# PCB_3.net
KiCad netlist of a schematic drawn in EAGLE
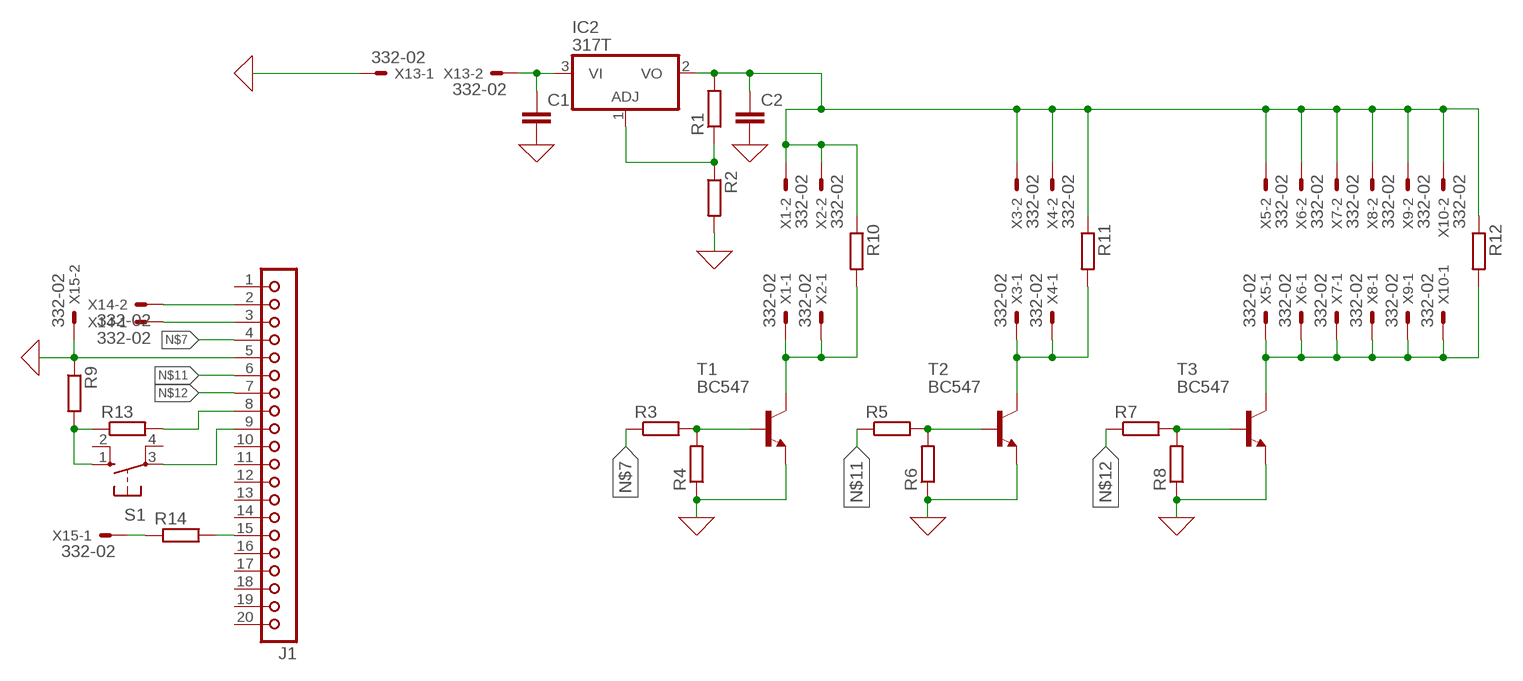
[diagram p0: schematic, sheet 1]

(export (version "E")
  (design (tool "Eeschema 10.0.6"))
  (components
    (comp (ref "C1")
      (value "C-EU050-025X075")
      (footprint "eagle-import:C050-025X075")
      (libsource (lib "eagle-import") (part "C-EU050-025X075"))
    )
    (comp (ref "C2")
      (value "C-EU050-025X075")
      (footprint "eagle-import:C050-025X075")
      (libsource (lib "eagle-import") (part "C-EU050-025X075"))
    )
    (comp (ref "IC2")
      (value "317T")
      (footprint "eagle-import:TO220H")
      (libsource (lib "eagle-import") (part "317T"))
    )
    (comp (ref "J1")
      (value "JBK20L")
      (footprint "eagle-import:JBK20L")
      (libsource (lib "eagle-import") (part "JBK20L"))
    )
    (comp (ref "R1")
      (value "R-EU_0309/12")
      (footprint "eagle-import:0309_12")
      (libsource (lib "eagle-import") (part "R-EU_0309/12"))
    )
    (comp (ref "R2")
      (value "R-EU_0309/12")
      (footprint "eagle-import:0309_12")
      (libsource (lib "eagle-import") (part "R-EU_0309/12"))
    )
    (comp (ref "R3")
      (value "R-EU_0309/12")
      (footprint "eagle-import:0309_12")
      (libsource (lib "eagle-import") (part "R-EU_0309/12"))
    )
    (comp (ref "R4")
      (value "R-EU_0309/12")
      (footprint "eagle-import:0309_12")
      (libsource (lib "eagle-import") (part "R-EU_0309/12"))
    )
    (comp (ref "R5")
      (value "R-EU_0309/12")
      (footprint "eagle-import:0309_12")
      (libsource (lib "eagle-import") (part "R-EU_0309/12"))
    )
    (comp (ref "R6")
      (value "R-EU_0309/12")
      (footprint "eagle-import:0309_12")
      (libsource (lib "eagle-import") (part "R-EU_0309/12"))
    )
    (comp (ref "R7")
      (value "R-EU_0309/12")
      (footprint "eagle-import:0309_12")
      (libsource (lib "eagle-import") (part "R-EU_0309/12"))
    )
    (comp (ref "R8")
      (value "R-EU_0309/12")
      (footprint "eagle-import:0309_12")
      (libsource (lib "eagle-import") (part "R-EU_0309/12"))
    )
    (comp (ref "R9")
      (value "R-EU_0309/12")
      (footprint "eagle-import:0309_12")
      (libsource (lib "eagle-import") (part "R-EU_0309/12"))
    )
    (comp (ref "R10")
      (value "R-EU_0309/12")
      (footprint "eagle-import:0309_12")
      (libsource (lib "eagle-import") (part "R-EU_0309/12"))
    )
    (comp (ref "R11")
      (value "R-EU_0309/12")
      (footprint "eagle-import:0309_12")
      (libsource (lib "eagle-import") (part "R-EU_0309/12"))
    )
    (comp (ref "R12")
      (value "R-EU_0309/12")
      (footprint "eagle-import:0309_12")
      (libsource (lib "eagle-import") (part "R-EU_0309/12"))
    )
    (comp (ref "R13")
      (value "R-EU_0309/12")
      (footprint "eagle-import:0309_12")
      (libsource (lib "eagle-import") (part "R-EU_0309/12"))
    )
    (comp (ref "R14")
      (value "R-EU_0309/12")
      (footprint "eagle-import:0309_12")
      (libsource (lib "eagle-import") (part "R-EU_0309/12"))
    )
    (comp (ref "S1")
      (value "10-XX")
      (footprint "eagle-import:B3F-10XX")
      (fields (field (name "MPN") "B3F-1000"))
      (libsource (lib "eagle-import") (part "10-XX"))
    )
    (comp (ref "T1")
      (value "BC547")
      (footprint "eagle-import:TO92")
      (libsource (lib "eagle-import") (part "BC547"))
    )
    (comp (ref "T2")
      (value "BC547")
      (footprint "eagle-import:TO92")
      (libsource (lib "eagle-import") (part "BC547"))
    )
    (comp (ref "T3")
      (value "BC547")
      (footprint "eagle-import:TO92")
      (libsource (lib "eagle-import") (part "BC547"))
    )
    (comp (ref "X1")
      (value "332-02")
      (footprint "eagle-import:332-02")
      (libsource (lib "eagle-import") (part "332-02"))
    )
    (comp (ref "X2")
      (value "332-02")
      (footprint "eagle-import:332-02")
      (libsource (lib "eagle-import") (part "332-02"))
    )
    (comp (ref "X3")
      (value "332-02")
      (footprint "eagle-import:332-02")
      (libsource (lib "eagle-import") (part "332-02"))
    )
    (comp (ref "X4")
      (value "332-02")
      (footprint "eagle-import:332-02")
      (libsource (lib "eagle-import") (part "332-02"))
    )
    (comp (ref "X5")
      (value "332-02")
      (footprint "eagle-import:332-02")
      (libsource (lib "eagle-import") (part "332-02"))
    )
    (comp (ref "X6")
      (value "332-02")
      (footprint "eagle-import:332-02")
      (libsource (lib "eagle-import") (part "332-02"))
    )
    (comp (ref "X7")
      (value "332-02")
      (footprint "eagle-import:332-02")
      (libsource (lib "eagle-import") (part "332-02"))
    )
    (comp (ref "X8")
      (value "332-02")
      (footprint "eagle-import:332-02")
      (libsource (lib "eagle-import") (part "332-02"))
    )
    (comp (ref "X9")
      (value "332-02")
      (footprint "eagle-import:332-02")
      (libsource (lib "eagle-import") (part "332-02"))
    )
    (comp (ref "X10")
      (value "332-02")
      (footprint "eagle-import:332-02")
      (libsource (lib "eagle-import") (part "332-02"))
    )
    (comp (ref "X13")
      (value "332-02")
      (footprint "eagle-import:332-02")
      (libsource (lib "eagle-import") (part "332-02"))
    )
    (comp (ref "X14")
      (value "332-02")
      (footprint "eagle-import:332-02")
      (libsource (lib "eagle-import") (part "332-02"))
    )
    (comp (ref "X15")
      (value "332-02")
      (footprint "eagle-import:332-02")
      (libsource (lib "eagle-import") (part "332-02"))
    )
  )
  (nets
    (net (code "1") (name "GND") (class "Default")
      (node (ref "C1") (pin "2") (pinfunction "2_2") (pintype "passive"))
      (node (ref "C2") (pin "2") (pinfunction "2_2") (pintype "passive"))
      (node (ref "J1") (pin "5") (pinfunction "5_5") (pintype "passive"))
      (node (ref "R2") (pin "2") (pinfunction "2_2") (pintype "passive"))
      (node (ref "R4") (pin "1") (pinfunction "1_1") (pintype "passive"))
      (node (ref "R6") (pin "1") (pinfunction "1_1") (pintype "passive"))
      (node (ref "R8") (pin "1") (pinfunction "1_1") (pintype "passive"))
      (node (ref "R9") (pin "1") (pinfunction "1_1") (pintype "passive"))
      (node (ref "T1") (pin "1") (pinfunction "E_1") (pintype "passive"))
      (node (ref "T2") (pin "1") (pinfunction "E_1") (pintype "passive"))
      (node (ref "T3") (pin "1") (pinfunction "E_1") (pintype "passive"))
      (node (ref "X13") (pin "1") (pinfunction "S_1") (pintype "passive"))
      (node (ref "X15") (pin "2") (pinfunction "S_2") (pintype "passive"))
    )
    (net (code "2") (name "N$7") (class "Default")
      (node (ref "J1") (pin "4") (pinfunction "4_4") (pintype "passive"))
      (node (ref "R3") (pin "1") (pinfunction "1_1") (pintype "passive"))
    )
    (net (code "3") (name "N$11") (class "Default")
      (node (ref "J1") (pin "6") (pinfunction "6_6") (pintype "passive"))
      (node (ref "R5") (pin "1") (pinfunction "1_1") (pintype "passive"))
    )
    (net (code "4") (name "N$12") (class "Default")
      (node (ref "J1") (pin "7") (pinfunction "7_7") (pintype "passive"))
      (node (ref "R7") (pin "1") (pinfunction "1_1") (pintype "passive"))
    )
    (net (code "5") (name "Net-(IC2-ADJ)") (class "Default")
      (node (ref "IC2") (pin "1") (pinfunction "ADJ_1") (pintype "input"))
      (node (ref "R1") (pin "1") (pinfunction "1_1") (pintype "passive"))
      (node (ref "R2") (pin "1") (pinfunction "1_1") (pintype "passive"))
    )
    (net (code "6") (name "Net-(IC2-VI)") (class "Default")
      (node (ref "C1") (pin "1") (pinfunction "1_1") (pintype "passive"))
      (node (ref "IC2") (pin "3") (pinfunction "VI_3") (pintype "input"))
      (node (ref "X13") (pin "2") (pinfunction "S_2") (pintype "passive"))
    )
    (net (code "7") (name "Net-(IC2-VO)") (class "Default")
      (node (ref "C2") (pin "1") (pinfunction "1_1") (pintype "passive"))
      (node (ref "IC2") (pin "2") (pinfunction "VO_2") (pintype "passive"))
      (node (ref "R1") (pin "2") (pinfunction "2_2") (pintype "passive"))
      (node (ref "R10") (pin "1") (pinfunction "1_1") (pintype "passive"))
      (node (ref "R11") (pin "1") (pinfunction "1_1") (pintype "passive"))
      (node (ref "R12") (pin "1") (pinfunction "1_1") (pintype "passive"))
      (node (ref "X1") (pin "2") (pinfunction "S_2") (pintype "passive"))
      (node (ref "X10") (pin "2") (pinfunction "S_2") (pintype "passive"))
      (node (ref "X2") (pin "2") (pinfunction "S_2") (pintype "passive"))
      (node (ref "X3") (pin "2") (pinfunction "S_2") (pintype "passive"))
      (node (ref "X4") (pin "2") (pinfunction "S_2") (pintype "passive"))
      (node (ref "X5") (pin "2") (pinfunction "S_2") (pintype "passive"))
      (node (ref "X6") (pin "2") (pinfunction "S_2") (pintype "passive"))
      (node (ref "X7") (pin "2") (pinfunction "S_2") (pintype "passive"))
      (node (ref "X8") (pin "2") (pinfunction "S_2") (pintype "passive"))
      (node (ref "X9") (pin "2") (pinfunction "S_2") (pintype "passive"))
    )
    (net (code "8") (name "Net-(J1-Pad8)") (class "Default")
      (node (ref "J1") (pin "8") (pinfunction "8_8") (pintype "passive"))
      (node (ref "R13") (pin "2") (pinfunction "2_2") (pintype "passive"))
    )
    (net (code "9") (name "Net-(J1-Pad15)") (class "Default")
      (node (ref "J1") (pin "15") (pinfunction "15_15") (pintype "passive"))
      (node (ref "R14") (pin "2") (pinfunction "2_2") (pintype "passive"))
    )
    (net (code "10") (name "Net-(S1-P)") (class "Default")
      (node (ref "J1") (pin "9") (pinfunction "9_9") (pintype "passive"))
      (node (ref "S1") (pin "3") (pinfunction "P_3") (pintype "passive"))
    )
    (net (code "11") (name "Net-(S1-S)") (class "Default")
      (node (ref "R13") (pin "1") (pinfunction "1_1") (pintype "passive"))
      (node (ref "R9") (pin "2") (pinfunction "2_2") (pintype "passive"))
      (node (ref "S1") (pin "1") (pinfunction "S_1") (pintype "passive"))
    )
    (net (code "12") (name "Net-(T1-B)") (class "Default")
      (node (ref "R3") (pin "2") (pinfunction "2_2") (pintype "passive"))
      (node (ref "R4") (pin "2") (pinfunction "2_2") (pintype "passive"))
      (node (ref "T1") (pin "2") (pinfunction "B_2") (pintype "passive"))
    )
    (net (code "13") (name "Net-(T1-C)") (class "Default")
      (node (ref "R10") (pin "2") (pinfunction "2_2") (pintype "passive"))
      (node (ref "T1") (pin "3") (pinfunction "C_3") (pintype "passive"))
      (node (ref "X1") (pin "1") (pinfunction "S_1") (pintype "passive"))
      (node (ref "X2") (pin "1") (pinfunction "S_1") (pintype "passive"))
    )
    (net (code "14") (name "Net-(T2-B)") (class "Default")
      (node (ref "R5") (pin "2") (pinfunction "2_2") (pintype "passive"))
      (node (ref "R6") (pin "2") (pinfunction "2_2") (pintype "passive"))
      (node (ref "T2") (pin "2") (pinfunction "B_2") (pintype "passive"))
    )
    (net (code "15") (name "Net-(T2-C)") (class "Default")
      (node (ref "R11") (pin "2") (pinfunction "2_2") (pintype "passive"))
      (node (ref "T2") (pin "3") (pinfunction "C_3") (pintype "passive"))
      (node (ref "X3") (pin "1") (pinfunction "S_1") (pintype "passive"))
      (node (ref "X4") (pin "1") (pinfunction "S_1") (pintype "passive"))
    )
    (net (code "16") (name "Net-(T3-B)") (class "Default")
      (node (ref "R7") (pin "2") (pinfunction "2_2") (pintype "passive"))
      (node (ref "R8") (pin "2") (pinfunction "2_2") (pintype "passive"))
      (node (ref "T3") (pin "2") (pinfunction "B_2") (pintype "passive"))
    )
    (net (code "17") (name "Net-(T3-C)") (class "Default")
      (node (ref "R12") (pin "2") (pinfunction "2_2") (pintype "passive"))
      (node (ref "T3") (pin "3") (pinfunction "C_3") (pintype "passive"))
      (node (ref "X10") (pin "1") (pinfunction "S_1") (pintype "passive"))
      (node (ref "X5") (pin "1") (pinfunction "S_1") (pintype "passive"))
      (node (ref "X6") (pin "1") (pinfunction "S_1") (pintype "passive"))
      (node (ref "X7") (pin "1") (pinfunction "S_1") (pintype "passive"))
      (node (ref "X8") (pin "1") (pinfunction "S_1") (pintype "passive"))
      (node (ref "X9") (pin "1") (pinfunction "S_1") (pintype "passive"))
    )
    (net (code "18") (name "Net-(X14A-S)") (class "Default")
      (node (ref "J1") (pin "3") (pinfunction "3_3") (pintype "passive"))
      (node (ref "X14") (pin "1") (pinfunction "S_1") (pintype "passive"))
    )
    (net (code "19") (name "Net-(X14B-S)") (class "Default")
      (node (ref "J1") (pin "2") (pinfunction "2_2") (pintype "passive"))
      (node (ref "X14") (pin "2") (pinfunction "S_2") (pintype "passive"))
    )
    (net (code "20") (name "Net-(X15A-S)") (class "Default")
      (node (ref "R14") (pin "1") (pinfunction "1_1") (pintype "passive"))
      (node (ref "X15") (pin "1") (pinfunction "S_1") (pintype "passive"))
    )
    (net (code "21") (name "unconnected-(J1-Pad1)") (class "Default")
      (node (ref "J1") (pin "1") (pinfunction "1_1") (pintype "passive"))
    )
    (net (code "22") (name "unconnected-(J1-Pad10)") (class "Default")
      (node (ref "J1") (pin "10") (pinfunction "10_10") (pintype "passive"))
    )
    (net (code "23") (name "unconnected-(J1-Pad11)") (class "Default")
      (node (ref "J1") (pin "11") (pinfunction "11_11") (pintype "passive"))
    )
    (net (code "24") (name "unconnected-(J1-Pad12)") (class "Default")
      (node (ref "J1") (pin "12") (pinfunction "12_12") (pintype "passive"))
    )
    (net (code "25") (name "unconnected-(J1-Pad13)") (class "Default")
      (node (ref "J1") (pin "13") (pinfunction "13_13") (pintype "passive"))
    )
    (net (code "26") (name "unconnected-(J1-Pad14)") (class "Default")
      (node (ref "J1") (pin "14") (pinfunction "14_14") (pintype "passive"))
    )
    (net (code "27") (name "unconnected-(J1-Pad16)") (class "Default")
      (node (ref "J1") (pin "16") (pinfunction "16_16") (pintype "passive"))
    )
    (net (code "28") (name "unconnected-(J1-Pad17)") (class "Default")
      (node (ref "J1") (pin "17") (pinfunction "17_17") (pintype "passive"))
    )
    (net (code "29") (name "unconnected-(J1-Pad18)") (class "Default")
      (node (ref "J1") (pin "18") (pinfunction "18_18") (pintype "passive"))
    )
    (net (code "30") (name "unconnected-(J1-Pad19)") (class "Default")
      (node (ref "J1") (pin "19") (pinfunction "19_19") (pintype "passive"))
    )
    (net (code "31") (name "unconnected-(J1-Pad20)") (class "Default")
      (node (ref "J1") (pin "20") (pinfunction "20_20") (pintype "passive"))
    )
    (net (code "32") (name "unconnected-(S1-P1-Pad4)") (class "Default")
      (node (ref "S1") (pin "4") (pinfunction "P1_4") (pintype "passive"))
    )
    (net (code "33") (name "unconnected-(S1-S1-Pad2)") (class "Default")
      (node (ref "S1") (pin "2") (pinfunction "S1_2") (pintype "passive"))
    )
  )
)
